# Accumulator_Indicator_PCB.net
KiCad netlist of a schematic drawn in Altium Designer
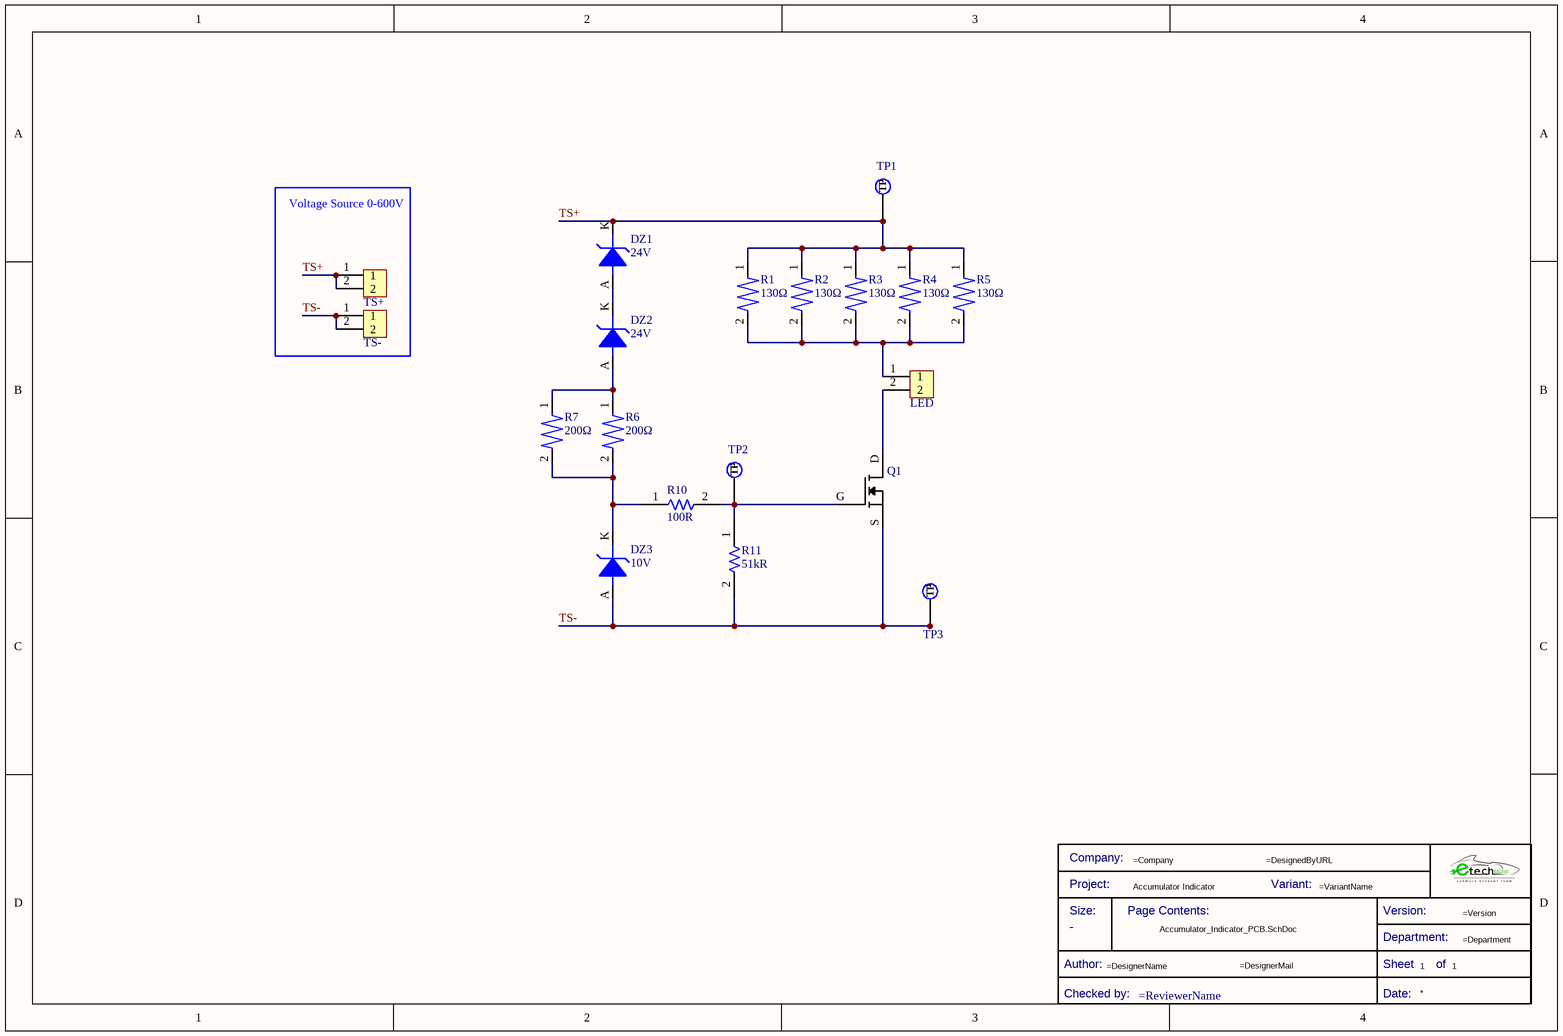
[diagram p0: Accumulator_Indicator_PCB.SchDoc]

(export (version "E")
  (design (tool "Eeschema 10.0.6"))
  (components
    (comp (ref "*")
      (value "Title Block_template")
      (description "Standard Title Block")
      (fields
        (field (name "SIZE") "-")
        (field (name ".CREATOR") "GP")
        (field (name ".PCBCHECK") "GP")
        (field (name ".SCHCHECK") "GP")
      )
      (libsource (lib "e-Tech_Racing") (part "Title Block_template"))
    )
    (comp (ref "DZ1")
      (value "24V")
      (footprint "DZ_24V_STD")
      (description "BZX55C24")
      (libsource (lib "AM_Schlib") (part "DZ_24V_STD"))
    )
    (comp (ref "DZ2")
      (value "24V")
      (footprint "DZ_24V_STD")
      (description "BZX55C24")
      (libsource (lib "AM_Schlib") (part "DZ_24V_STD"))
    )
    (comp (ref "DZ3")
      (value "10V")
      (footprint "DZ_24V_BZT52H-A10-Q")
      (libsource (lib "AM_Schlib") (part "DZ_24V_BZT52H-A10-Q"))
    )
    (comp (ref "LED")
      (value "436500215")
      (footprint "J_MicroFit_2x1")
      (description "Header 1 Row Vertical Polarizing Peg 2 Pin SMT/Glow Wire Compatible Tin Plate")
      (libsource (lib "Electromechanical") (part "J_MicroFit_2x1"))
    )
    (comp (ref "Q1")
      (value "D2PAK type-A")
      (footprint "MOSFET-N-D2PAK")
      (description "STB36N60M6")
      (libsource (lib "AM_Schlib") (part "MOSFET-N-D2PAK"))
    )
    (comp (ref "R1")
      (value "130Ω")
      (footprint "R130K_3W413")
      (libsource (lib "AM_Schlib") (part "R130K_3W413"))
    )
    (comp (ref "R2")
      (value "130Ω")
      (footprint "R130K_3W413")
      (libsource (lib "AM_Schlib") (part "R130K_3W413"))
    )
    (comp (ref "R3")
      (value "130Ω")
      (footprint "R130K_3W413")
      (libsource (lib "AM_Schlib") (part "R130K_3W413"))
    )
    (comp (ref "R4")
      (value "130Ω")
      (footprint "R130K_3W413")
      (libsource (lib "AM_Schlib") (part "R130K_3W413"))
    )
    (comp (ref "R5")
      (value "130Ω")
      (footprint "R130K_3W413")
      (libsource (lib "AM_Schlib") (part "R130K_3W413"))
    )
    (comp (ref "R6") (value "200Ω") (footprint "R200K_2W") (libsource (lib "AM_Schlib") (part "R200K_2W")))
    (comp (ref "R7") (value "200Ω") (footprint "R200K_2W") (libsource (lib "AM_Schlib") (part "R200K_2W")))
    (comp (ref "R10")
      (value "CRG1206F100R")
      (footprint "R1206FTK-W")
      (description "Res Thick Film 1206 100 Ohm 1% 0.25W(1/4W) ±200ppm/C Pad SMD T/R")
      (fields
        (field (name "MANUFACTURER") "TE Connectivity")
        (field (name "TOLERANCE") "1%")
        (field (name "RESISTANCE") "100R")
        (field (name ".CREATOR") "AC")
      )
      (libsource (lib "Passives") (part "R100-1206FTK"))
    )
    (comp (ref "R11")
      (value "CRCW120610K0FKEA")
      (footprint "R1206FTK-W")
      (description "Res Thick Film 1206 51K Ohm 1% 1/4W ±100ppm/°C Molded SMD SMD Punched Carrier T/R")
      (fields
        (field (name "MANUFACTURER") "Panasonic")
        (field (name "MANUFACTURER PART NUMBER") "ERJ-S08F5102V")
        (field (name "RESISTANCE") "51kR")
        (field (name ".CREATOR") "DO")
      )
      (libsource (lib "Passives") (part "R51k-1206FTK"))
    )
    (comp (ref "TP1")
      (value "TestPoint")
      (footprint "TestPoint")
      (description "Test Point 1x1 mm")
      (fields (field (name ".CREATOR") "GP") (field (name ".PCBCHECK") "GP") (field (name ".SCHCHECK") "GP"))
      (libsource (lib "e-Tech_Racing") (part "TestPoint"))
    )
    (comp (ref "TP2")
      (value "TestPoint")
      (footprint "TestPoint")
      (description "Test Point 1x1 mm")
      (fields (field (name ".CREATOR") "GP") (field (name ".PCBCHECK") "GP") (field (name ".SCHCHECK") "GP"))
      (libsource (lib "e-Tech_Racing") (part "TestPoint"))
    )
    (comp (ref "TP3")
      (value "TestPoint")
      (footprint "TestPoint")
      (description "Test Point 1x1 mm")
      (fields (field (name ".CREATOR") "GP") (field (name ".PCBCHECK") "GP") (field (name ".SCHCHECK") "GP"))
      (libsource (lib "e-Tech_Racing") (part "TestPoint"))
    )
    (comp (ref "TS+")
      (value "436500215")
      (footprint "J_MicroFit_2x1")
      (description "Header 1 Row Vertical Polarizing Peg 2 Pin SMT/Glow Wire Compatible Tin Plate")
      (libsource (lib "Electromechanical") (part "J_MicroFit_2x1"))
    )
    (comp (ref "TS-")
      (value "436500215")
      (footprint "J_MicroFit_2x1")
      (description "Header 1 Row Vertical Polarizing Peg 2 Pin SMT/Glow Wire Compatible Tin Plate")
      (libsource (lib "Electromechanical") (part "J_MicroFit_2x1"))
    )
  )
  (nets
    (net (code "1") (name "/TS+") (class "Default")
      (node (ref "DZ1") (pin "K") (pinfunction "K_K") (pintype "passive"))
      (node (ref "R1") (pin "1") (pinfunction "1_1") (pintype "passive"))
      (node (ref "R2") (pin "1") (pinfunction "1_1") (pintype "passive"))
      (node (ref "R3") (pin "1") (pinfunction "1_1") (pintype "passive"))
      (node (ref "R4") (pin "1") (pinfunction "1_1") (pintype "passive"))
      (node (ref "R5") (pin "1") (pinfunction "1_1") (pintype "passive"))
      (node (ref "TP1") (pin "1") (pinfunction "TP_1") (pintype "passive"))
      (node (ref "TS+") (pin "1") (pinfunction "1_1") (pintype "passive"))
      (node (ref "TS+") (pin "2") (pinfunction "2_2") (pintype "passive"))
    )
    (net (code "2") (name "/TS-") (class "Default")
      (node (ref "DZ3") (pin "A") (pinfunction "A_A") (pintype "passive"))
      (node (ref "Q1") (pin "S") (pinfunction "S_S") (pintype "passive"))
      (node (ref "R11") (pin "2") (pinfunction "2_2") (pintype "passive"))
      (node (ref "TP3") (pin "1") (pinfunction "TP_1") (pintype "passive"))
      (node (ref "TS-") (pin "1") (pinfunction "1_1") (pintype "passive"))
      (node (ref "TS-") (pin "2") (pinfunction "2_2") (pintype "passive"))
    )
    (net (code "3") (name "Net-(DZ1-PadA)") (class "Default")
      (node (ref "DZ1") (pin "A") (pinfunction "A_A") (pintype "passive"))
      (node (ref "DZ2") (pin "K") (pinfunction "K_K") (pintype "passive"))
    )
    (net (code "4") (name "Net-(DZ2-PadA)") (class "Default")
      (node (ref "DZ2") (pin "A") (pinfunction "A_A") (pintype "passive"))
      (node (ref "R6") (pin "1") (pinfunction "1_1") (pintype "passive"))
      (node (ref "R7") (pin "1") (pinfunction "1_1") (pintype "passive"))
    )
    (net (code "5") (name "Net-(DZ3-PadK)") (class "Default")
      (node (ref "DZ3") (pin "K") (pinfunction "K_K") (pintype "passive"))
      (node (ref "R10") (pin "1") (pinfunction "1_1") (pintype "passive"))
      (node (ref "R6") (pin "2") (pinfunction "2_2") (pintype "passive"))
      (node (ref "R7") (pin "2") (pinfunction "2_2") (pintype "passive"))
    )
    (net (code "6") (name "Net-(LED-Pad1)") (class "Default")
      (node (ref "LED") (pin "1") (pinfunction "1_1") (pintype "passive"))
      (node (ref "R1") (pin "2") (pinfunction "2_2") (pintype "passive"))
      (node (ref "R2") (pin "2") (pinfunction "2_2") (pintype "passive"))
      (node (ref "R3") (pin "2") (pinfunction "2_2") (pintype "passive"))
      (node (ref "R4") (pin "2") (pinfunction "2_2") (pintype "passive"))
      (node (ref "R5") (pin "2") (pinfunction "2_2") (pintype "passive"))
    )
    (net (code "7") (name "Net-(LED-Pad2)") (class "Default")
      (node (ref "LED") (pin "2") (pinfunction "2_2") (pintype "passive"))
      (node (ref "Q1") (pin "D") (pinfunction "D_D") (pintype "passive"))
    )
    (net (code "8") (name "Net-(TP2-TP)") (class "Default")
      (node (ref "Q1") (pin "G") (pinfunction "G_G") (pintype "passive"))
      (node (ref "R10") (pin "2") (pinfunction "2_2") (pintype "passive"))
      (node (ref "R11") (pin "1") (pinfunction "1_1") (pintype "passive"))
      (node (ref "TP2") (pin "1") (pinfunction "TP_1") (pintype "passive"))
    )
  )
)
